# 2_-_WIDORA.net
KiCad netlist of a schematic drawn in Altium Designer
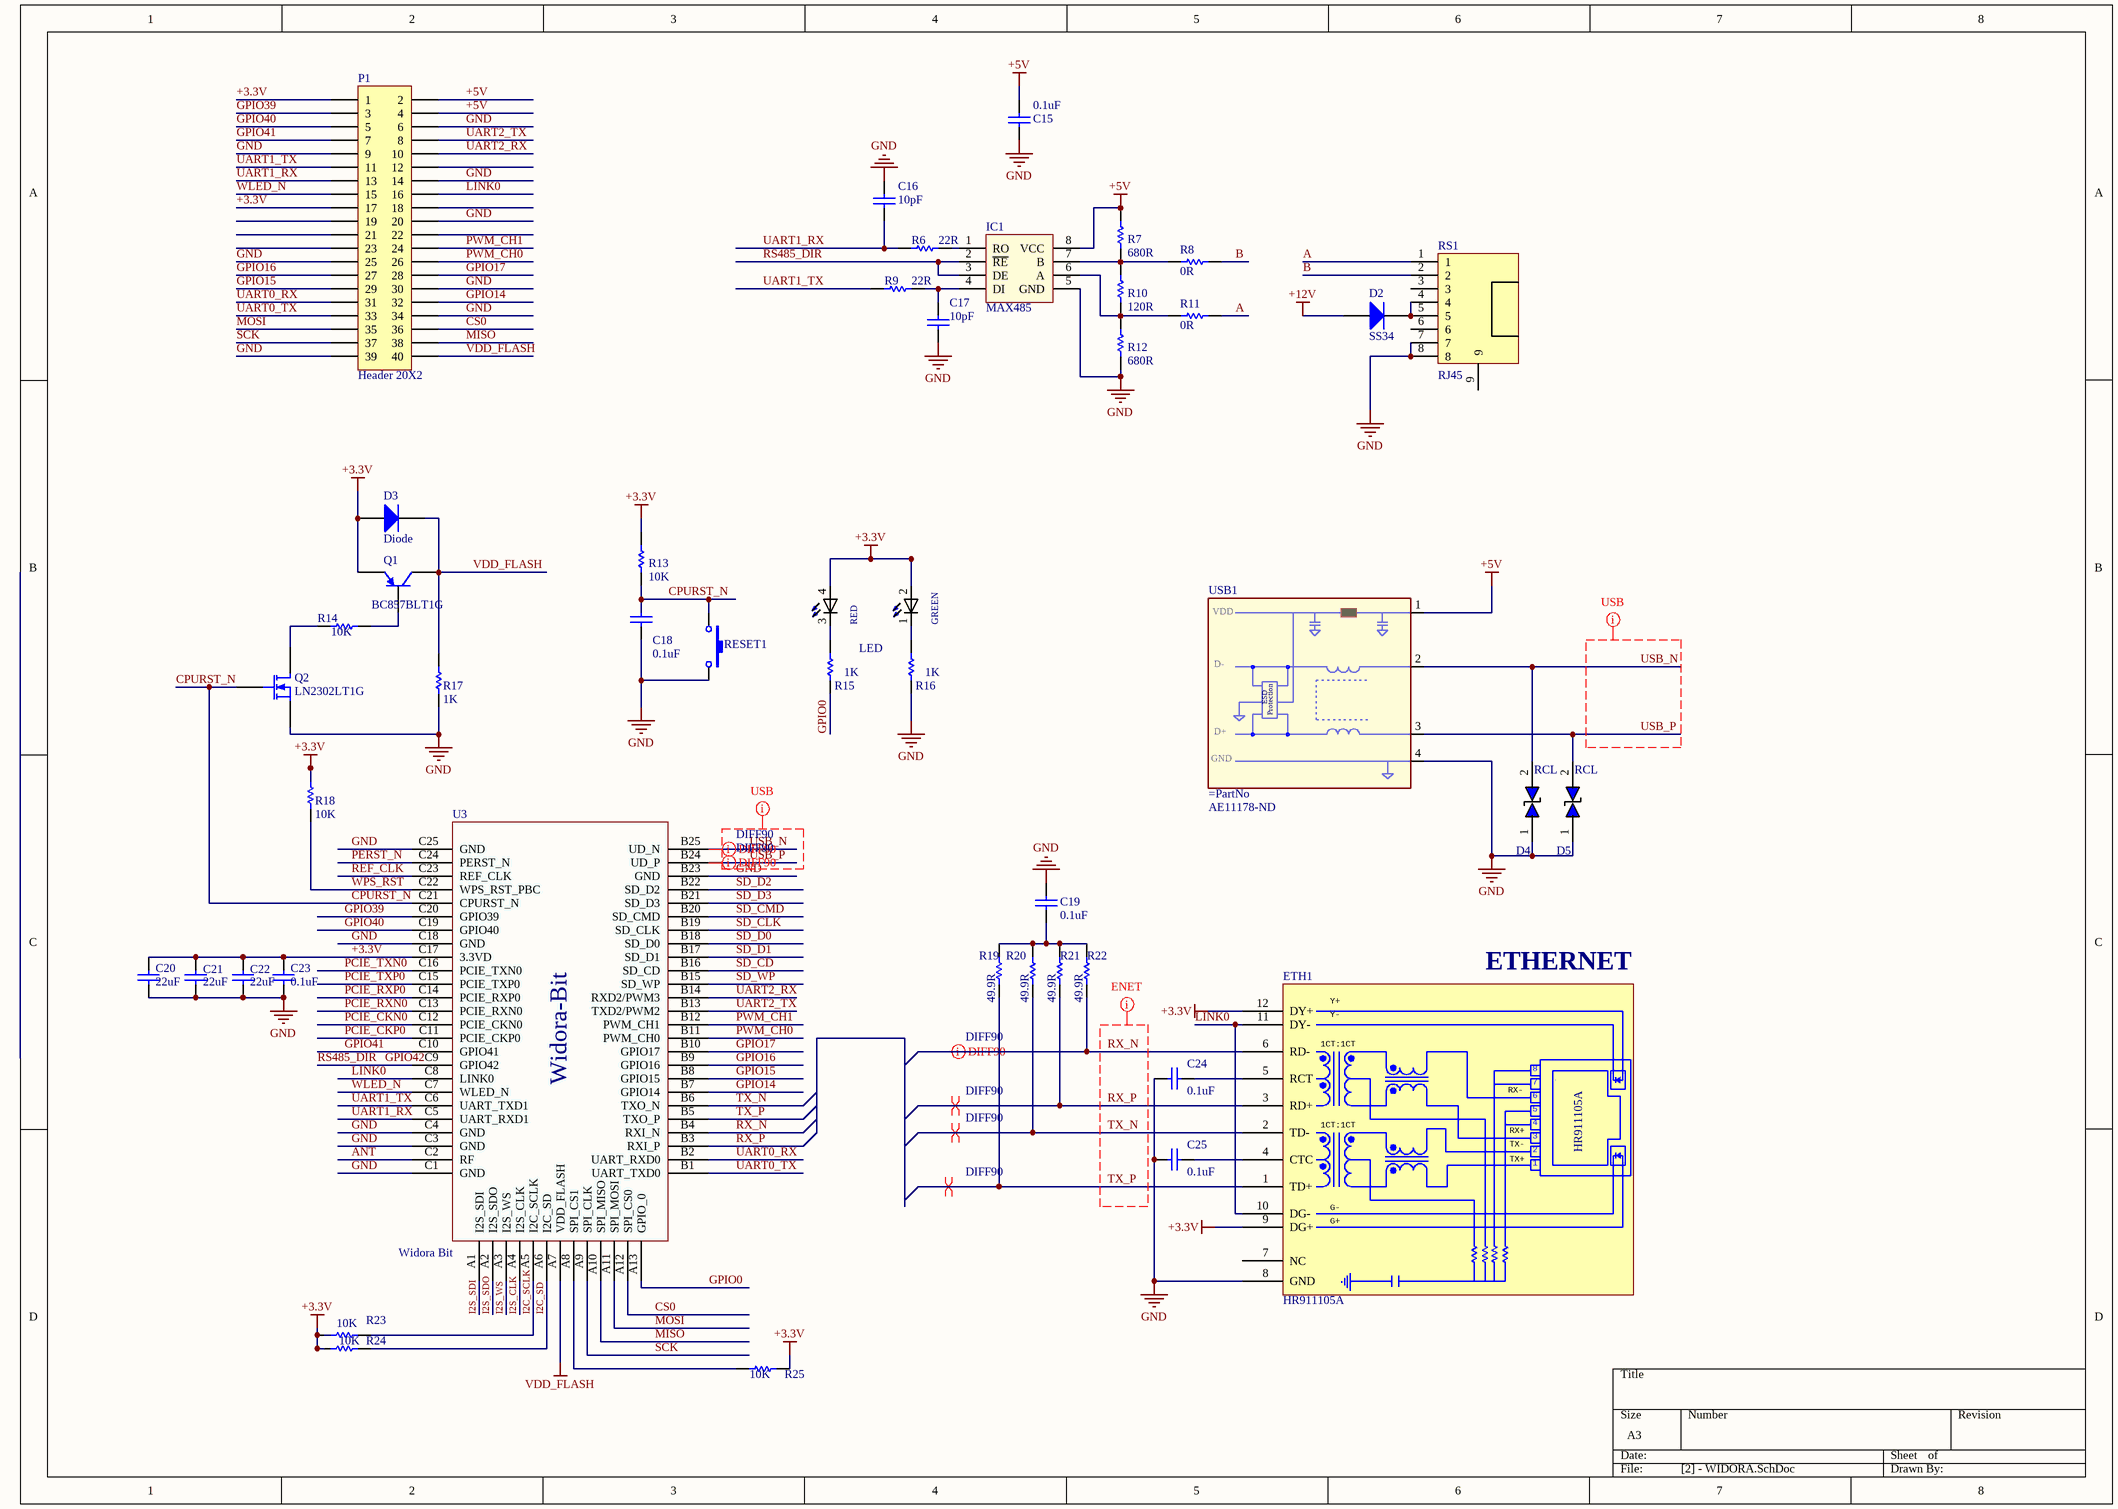
[diagram p0: [2] - WIDORA.SchDoc]

(export (version "E")
  (design (tool "Eeschema 10.0.6"))
  (components
    (comp (ref "C15")
      (value "0.1uF")
      (footprint "CN-SMD-0603")
      (description "CC0603KPX7R9BB104 0603 0.1 uF 50 V ±10% Tolerance X7R SMT Multilayer Ceramic Capacitor")
      (fields (field (name "TOLERANCE") "10%"))
      (libsource (lib "IOT_HIEP") (part "CN0603-0.1uF"))
    )
    (comp (ref "C16")
      (value "10pF")
      (footprint "CN-SMD-0603")
      (description "CC0603JRNPO9BN100 Surface Mount Ceramic Multilayer Capacitor 10pF 5% C0G 50V 0603 Paper T/R")
      (fields (field (name "TOLERANCE") "5%") (field (name "VOLTAGE") "50V"))
      (libsource (lib "IOT_HIEP") (part "CN0603-10pF"))
    )
    (comp (ref "C17")
      (value "10pF")
      (footprint "CN-SMD-0603")
      (description "CC0603JRNPO9BN100 Surface Mount Ceramic Multilayer Capacitor 10pF 5% C0G 50V 0603 Paper T/R")
      (fields (field (name "TOLERANCE") "5%") (field (name "VOLTAGE") "50V"))
      (libsource (lib "IOT_HIEP") (part "CN0603-10pF"))
    )
    (comp (ref "C18")
      (value "0.1uF")
      (footprint "CN-SMD-0603")
      (description "CC0603KPX7R9BB104 0603 0.1 uF 50 V ±10% Tolerance X7R SMT Multilayer Ceramic Capacitor")
      (fields (field (name "TOLERANCE") "10%"))
      (libsource (lib "IOT_HIEP") (part "CN0603-0.1uF"))
    )
    (comp (ref "C19")
      (value "0.1uF")
      (footprint "CN-SMD-0603")
      (description "CC0603KPX7R9BB104 0603 0.1 uF 50 V ±10% Tolerance X7R SMT Multilayer Ceramic Capacitor")
      (fields (field (name "TOLERANCE") "10%"))
      (libsource (lib "IOT_HIEP") (part "CN0603-0.1uF"))
    )
    (comp (ref "C20")
      (value "22uF")
      (footprint "CN-SMD-0805")
      (description "CC0805MKX5R6BB226 0805 22 uF 10 V ±20 % Tolerance X5R SMT Multilayer Ceramic Capacitor")
      (fields (field (name "TOLERANCE") "20%"))
      (libsource (lib "IOT_HIEP") (part "CN0805-22uF"))
    )
    (comp (ref "C21")
      (value "22uF")
      (footprint "CN-SMD-0805")
      (description "CC0805MKX5R6BB226 0805 22 uF 10 V ±20 % Tolerance X5R SMT Multilayer Ceramic Capacitor")
      (fields (field (name "TOLERANCE") "20%"))
      (libsource (lib "IOT_HIEP") (part "CN0805-22uF"))
    )
    (comp (ref "C22")
      (value "22uF")
      (footprint "CN-SMD-0805")
      (description "CC0805MKX5R6BB226 0805 22 uF 10 V ±20 % Tolerance X5R SMT Multilayer Ceramic Capacitor")
      (fields (field (name "TOLERANCE") "20%"))
      (libsource (lib "IOT_HIEP") (part "CN0805-22uF"))
    )
    (comp (ref "C23")
      (value "0.1uF")
      (footprint "CN-SMD-0603")
      (description "CC0603KPX7R9BB104 0603 0.1 uF 50 V ±10% Tolerance X7R SMT Multilayer Ceramic Capacitor")
      (fields (field (name "TOLERANCE") "10%"))
      (libsource (lib "IOT_HIEP") (part "CN0603-0.1uF"))
    )
    (comp (ref "C24")
      (value "0.1uF")
      (footprint "CN-SMD-0603")
      (description "CC0603KPX7R9BB104 0603 0.1 uF 50 V ±10% Tolerance X7R SMT Multilayer Ceramic Capacitor")
      (fields (field (name "TOLERANCE") "10%"))
      (libsource (lib "IOT_HIEP") (part "CN0603-0.1uF"))
    )
    (comp (ref "C25")
      (value "0.1uF")
      (footprint "CN-SMD-0603")
      (description "CC0603KPX7R9BB104 0603 0.1 uF 50 V ±10% Tolerance X7R SMT Multilayer Ceramic Capacitor")
      (fields (field (name "TOLERANCE") "10%"))
      (libsource (lib "IOT_HIEP") (part "CN0603-0.1uF"))
    )
    (comp (ref "D2")
      (value "SS34")
      (footprint "DO-214AC")
      (description "SS34 DIODE SCHOTTKY 40V 3A SMC")
      (fields (field (name "VOLTAGE") "40V"))
      (libsource (lib "IOT_HIEP") (part "Diode_SS34"))
    )
    (comp (ref "D3")
      (value "Diode")
      (footprint "SOD323")
      (description "Default Diode")
      (fields (field (name "PUBLISHER") "Altium Limited"))
      (libsource (lib "IOT_DAT") (part "Diode"))
    )
    (comp (ref "D4")
      (value "RCL")
      (footprint "RES-0603")
      (description "ESD Suppressor TVS Â±20KV 2-Pin SLP1006P2T T/R")
      (fields (field (name "MP") "RCLAMP0531TQTCT") (field (name "MF") "Semtech Corporation"))
      (libsource (lib "RCLAMP0531TQTCT") (part "RCLAMP0531TQTCT"))
    )
    (comp (ref "D5")
      (value "RCL")
      (footprint "RES-0603")
      (description "ESD Suppressor TVS Â±20KV 2-Pin SLP1006P2T T/R")
      (fields (field (name "MP") "RCLAMP0531TQTCT") (field (name "MF") "Semtech Corporation"))
      (libsource (lib "RCLAMP0531TQTCT") (part "RCLAMP0531TQTCT"))
    )
    (comp (ref "ETH1")
      (value "HR911105A")
      (footprint "HR911105A")
      (fields (field (name "MANUFACTURER") "Hanrun"))
      (libsource (lib "NestHouse") (part "RJ45 - Tranfomer"))
    )
    (comp (ref "IC1")
      (value "MAX485")
      (footprint "SO8")
      (description "RS232 - RS485 (Same sn75176)")
      (libsource (lib "Library AL") (part "MAX485"))
    )
    (comp (ref "LED")
      (value "122-000-04-52")
      (footprint "*122-000-04-52_122-000-04-52(Primary)")
      (fields (field (name "MF") "Marl"))
      (libsource (lib "122-000-04-52") (part "122-000-04-52"))
    )
    (comp (ref "P1")
      (value "Header 20X2")
      (footprint "HDR2X20")
      (description "Header, 20-Pin, Dual row")
      (fields (field (name "PUBLISHER") "Altium Limited"))
      (libsource (lib "IOT_DAT") (part "Header 20X2"))
    )
    (comp (ref "Q1")
      (value "BC857BLT1G")
      (footprint "SOT-23B_L")
      (description "PNP Bipolar Transistor")
      (fields
        (field (name "MANUFACTURER") "ON Semiconductor")
        (field (name "MANUFACTURER PART NUMBER") "SBC857BLT1G")
      )
      (libsource (lib "NestHouse") (part "BC857BLT1G"))
    )
    (comp (ref "Q2")
      (value "LN2302LT1G")
      (footprint "SOT-23B_L")
      (description "N-Channel MOSFET")
      (fields (field (name "MANUFACTURER") "LRC"))
      (libsource (lib "NestHouse") (part "MOSFET-N"))
    )
    (comp (ref "R6")
      (value "22R")
      (footprint "RES 0603")
      (description "311-22GRCT-ND Res Thick Film 0603 22 Ohm 5% 0.1W(1/10W) ±100ppm/C Pad SMD T/R")
      (fields (field (name "TOLERANCE") "5%"))
      (libsource (lib "IOT_HIEP") (part "RC0603_22R"))
    )
    (comp (ref "R7")
      (value "680R")
      (footprint "RES 0603")
      (description "AC0603JR-07680RL Res Thick Film 0603 680 Ohm 5% 0.1W(1/10W) +/-100ppm/ßC Epoxy SMD Automotive T/R")
      (fields (field (name "TOLERANCE") "5%"))
      (libsource (lib "IOT_HIEP") (part "RC0603_680R"))
    )
    (comp (ref "R8")
      (value "0R")
      (footprint "RES 0603")
      (description "AC0603JR-070RL Res Thick Film 0603 0 Ohm Jumper 1/10W Molded SMD Paper T/R")
      (fields (field (name "TOLERANCE") "1%"))
      (libsource (lib "IOT_HIEP") (part "RC0603_0R"))
    )
    (comp (ref "R9")
      (value "22R")
      (footprint "RES 0603")
      (description "311-22GRCT-ND Res Thick Film 0603 22 Ohm 5% 0.1W(1/10W) ±100ppm/C Pad SMD T/R")
      (fields (field (name "TOLERANCE") "5%"))
      (libsource (lib "IOT_HIEP") (part "RC0603_22R"))
    )
    (comp (ref "R10")
      (value "120R")
      (footprint "RES 0603")
      (description "RC0603JR-07120RL Res Thick Film 0603 120 Ohm 5% 0.1W(1/10W) ±100ppm/C Pad SMD T/R")
      (fields (field (name "TOLERANCE") "5%"))
      (libsource (lib "IOT_HIEP") (part "RC0603_120R"))
    )
    (comp (ref "R11")
      (value "0R")
      (footprint "RES 0603")
      (description "AC0603JR-070RL Res Thick Film 0603 0 Ohm Jumper 1/10W Molded SMD Paper T/R")
      (fields (field (name "TOLERANCE") "1%"))
      (libsource (lib "IOT_HIEP") (part "RC0603_0R"))
    )
    (comp (ref "R12")
      (value "680R")
      (footprint "RES 0603")
      (description "AC0603JR-07680RL Res Thick Film 0603 680 Ohm 5% 0.1W(1/10W) +/-100ppm/ßC Epoxy SMD Automotive T/R")
      (fields (field (name "TOLERANCE") "5%"))
      (libsource (lib "IOT_HIEP") (part "RC0603_680R"))
    )
    (comp (ref "R13")
      (value "10K")
      (footprint "RES 0603")
      (description "AC0603FR-0710KL Res Thick Film 0603 10K Ohm 1% 0.1W(1/10W) ±100ppm/C Pad SMD Automotive T/R")
      (fields (field (name "TOLERANCE") "1%"))
      (libsource (lib "IOT_HIEP") (part "RC0603_10K"))
    )
    (comp (ref "R14")
      (value "10K")
      (footprint "RES 0603")
      (description "AC0603FR-0710KL Res Thick Film 0603 10K Ohm 1% 0.1W(1/10W) ±100ppm/C Pad SMD Automotive T/R")
      (fields (field (name "TOLERANCE") "1%") (field (name "SUPPLIER PART NUMBER 1") "10K"))
      (libsource (lib "IOT_HIEP") (part "RC0603_10K"))
    )
    (comp (ref "R15")
      (value "1K")
      (footprint "RES 0603")
      (fields (field (name "TOLERANCE") "5%"))
      (libsource (lib "IOT_HIEP") (part "RC0603_1K"))
    )
    (comp (ref "R16")
      (value "1K")
      (footprint "RES 0603")
      (fields (field (name "TOLERANCE") "5%"))
      (libsource (lib "IOT_HIEP") (part "RC0603_1K"))
    )
    (comp (ref "R17")
      (value "1K")
      (footprint "RES 0603")
      (fields (field (name "TOLERANCE") "5%"))
      (libsource (lib "IOT_HIEP") (part "RC0603_1K"))
    )
    (comp (ref "R18")
      (value "10K")
      (footprint "RES 0603")
      (description "AC0603FR-0710KL Res Thick Film 0603 10K Ohm 1% 0.1W(1/10W) ±100ppm/C Pad SMD Automotive T/R")
      (fields (field (name "TOLERANCE") "1%"))
      (libsource (lib "IOT_HIEP") (part "RC0603_10K"))
    )
    (comp (ref "R19")
      (value "49.9R")
      (footprint "RES 0603")
      (description "YAG5744CT-ND Res Thin Film 0603 49.9 Ohm 1% 1/10W ±50ppm/°C Molded SMD SMD Paper T/R")
      (fields (field (name "TOLERANCE") "1%"))
      (libsource (lib "IOT_HIEP") (part "RC0603_49.9R"))
    )
    (comp (ref "R20")
      (value "49.9R")
      (footprint "RES 0603")
      (description "YAG5744CT-ND Res Thin Film 0603 49.9 Ohm 1% 1/10W ±50ppm/°C Molded SMD SMD Paper T/R")
      (fields (field (name "TOLERANCE") "1%"))
      (libsource (lib "IOT_HIEP") (part "RC0603_49.9R"))
    )
    (comp (ref "R21")
      (value "49.9R")
      (footprint "RES 0603")
      (description "YAG5744CT-ND Res Thin Film 0603 49.9 Ohm 1% 1/10W ±50ppm/°C Molded SMD SMD Paper T/R")
      (fields (field (name "TOLERANCE") "1%"))
      (libsource (lib "IOT_HIEP") (part "RC0603_49.9R"))
    )
    (comp (ref "R22")
      (value "49.9R")
      (footprint "RES 0603")
      (description "YAG5744CT-ND Res Thin Film 0603 49.9 Ohm 1% 1/10W ±50ppm/°C Molded SMD SMD Paper T/R")
      (fields (field (name "TOLERANCE") "1%"))
      (libsource (lib "IOT_HIEP") (part "RC0603_49.9R"))
    )
    (comp (ref "R23")
      (value "10K")
      (footprint "RES 0603")
      (description "AC0603FR-0710KL Res Thick Film 0603 10K Ohm 1% 0.1W(1/10W) ±100ppm/C Pad SMD Automotive T/R")
      (fields (field (name "TOLERANCE") "1%"))
      (libsource (lib "IOT_HIEP") (part "RC0603_10K"))
    )
    (comp (ref "R24")
      (value "10K")
      (footprint "RES 0603")
      (description "AC0603FR-0710KL Res Thick Film 0603 10K Ohm 1% 0.1W(1/10W) ±100ppm/C Pad SMD Automotive T/R")
      (fields (field (name "TOLERANCE") "1%"))
      (libsource (lib "IOT_HIEP") (part "RC0603_10K"))
    )
    (comp (ref "R25")
      (value "10K")
      (footprint "RES 0603")
      (description "AC0603FR-0710KL Res Thick Film 0603 10K Ohm 1% 0.1W(1/10W) ±100ppm/C Pad SMD Automotive T/R")
      (fields (field (name "TOLERANCE") "1%"))
      (libsource (lib "IOT_HIEP") (part "RC0603_10K"))
    )
    (comp (ref "RESET1")
      (value "SW-SMD")
      (footprint "SW2-D2 - duplicate")
      (description "Switch")
      (fields (field (name "PUBLISHER") "Altium Limited"))
      (libsource (lib "NBBLib 14-03-2012") (part "SW-SMD"))
    )
    (comp (ref "RS1")
      (value "RJ45")
      (footprint "RJ45_8PIN_VOSAT_V2")
      (libsource (lib "Library_HoangAnh") (part "RJ45"))
    )
    (comp (ref "U3")
      (value "Widora Bit")
      (footprint "WIDORA")
      (description "Widora MT7688")
      (fields
        (field (name "MANUFACTURER") "Widora")
        (field (name "MANUFACTURER PART NUMBER") "Widora Bit 3 MT7688")
      )
      (libsource (lib "NestHouse") (part "Widora"))
    )
    (comp (ref "USB1")
      (value "~")
      (footprint "USB A Vertical")
      (description "THT USB 2.0 A Connector WE-EPLE")
      (fields
        (field (name "MANUFACTURER") "ASSMANN WSW Components")
        (field (name "MANUFACTURER PART NUMBER") "A-USB A-E")
        (field (name "SUPPLIER PART NUMBER 1") "AE11178-ND")
      )
      (libsource (lib "NestHouse") (part "USB-4"))
    )
  )
  (nets
    (net (code "1") (name "+3.3V") (class "Default")
      (node (ref "C20") (pin "2") (pinfunction "2_2") (pintype "passive"))
      (node (ref "C21") (pin "2") (pinfunction "2_2") (pintype "passive"))
      (node (ref "C22") (pin "2") (pinfunction "2_2") (pintype "passive"))
      (node (ref "C23") (pin "1") (pinfunction "1_1") (pintype "passive"))
      (node (ref "D3") (pin "1") (pinfunction "A_1") (pintype "passive"))
      (node (ref "ETH1") (pin "12") (pinfunction "DY+_12") (pintype "passive"))
      (node (ref "ETH1") (pin "9") (pinfunction "DG+_9") (pintype "passive"))
      (node (ref "LED") (pin "2") (pinfunction "GA_2") (pintype "passive"))
      (node (ref "LED") (pin "4") (pinfunction "RA_4") (pintype "passive"))
      (node (ref "P1") (pin "1") (pinfunction "1_1") (pintype "passive"))
      (node (ref "P1") (pin "17") (pinfunction "17_17") (pintype "passive"))
      (node (ref "Q1") (pin "2") (pinfunction "E_2") (pintype "passive"))
      (node (ref "R13") (pin "2") (pinfunction "2_2") (pintype "passive"))
      (node (ref "R18") (pin "2") (pinfunction "2_2") (pintype "passive"))
      (node (ref "R23") (pin "2") (pinfunction "2_2") (pintype "passive"))
      (node (ref "R24") (pin "2") (pinfunction "2_2") (pintype "passive"))
      (node (ref "R25") (pin "1") (pinfunction "1_1") (pintype "passive"))
      (node (ref "U3") (pin "C17") (pinfunction "3.3VD_C17") (pintype "passive"))
    )
    (net (code "2") (name "+5V") (class "Default")
      (node (ref "C15") (pin "2") (pinfunction "2_2") (pintype "passive"))
      (node (ref "IC1") (pin "8") (pinfunction "VCC_8") (pintype "passive"))
      (node (ref "P1") (pin "2") (pinfunction "2_2") (pintype "passive"))
      (node (ref "P1") (pin "4") (pinfunction "4_4") (pintype "passive"))
      (node (ref "R7") (pin "2") (pinfunction "2_2") (pintype "passive"))
      (node (ref "USB1") (pin "1") (pinfunction "VBUS_1") (pintype "passive"))
    )
    (net (code "3") (name "+12V") (class "Default")
      (node (ref "D2") (pin "1") (pinfunction "A_1") (pintype "passive"))
    )
    (net (code "4") (name "/A") (class "Default")
      (node (ref "R11") (pin "2") (pinfunction "2_2") (pintype "passive"))
      (node (ref "RS1") (pin "1") (pinfunction "1_1") (pintype "passive"))
    )
    (net (code "5") (name "/ANT") (class "Default")
      (node (ref "U3") (pin "C2") (pinfunction "RF_C2") (pintype "passive"))
    )
    (net (code "6") (name "/B") (class "Default")
      (node (ref "R8") (pin "2") (pinfunction "2_2") (pintype "passive"))
      (node (ref "RS1") (pin "2") (pinfunction "2_2") (pintype "passive"))
    )
    (net (code "7") (name "/CPURST_N") (class "Default")
      (node (ref "C18") (pin "2") (pinfunction "2_2") (pintype "passive"))
      (node (ref "Q2") (pin "1") (pinfunction "G_1") (pintype "passive"))
      (node (ref "R13") (pin "1") (pinfunction "1_1") (pintype "passive"))
      (node (ref "RESET1") (pin "1") (pinfunction "1_1") (pintype "passive"))
      (node (ref "U3") (pin "C21") (pinfunction "CPURST_N_C21") (pintype "passive"))
    )
    (net (code "8") (name "/CS0") (class "Default")
      (node (ref "P1") (pin "36") (pinfunction "36_36") (pintype "passive"))
      (node (ref "U3") (pin "A12") (pinfunction "SPI_CS0_A12") (pintype "passive"))
    )
    (net (code "9") (name "/GPIO0") (class "Default")
      (node (ref "R15") (pin "1") (pinfunction "1_1") (pintype "passive"))
      (node (ref "U3") (pin "A13") (pinfunction "GPIO_0_A13") (pintype "passive"))
    )
    (net (code "10") (name "/GPIO14") (class "Default")
      (node (ref "P1") (pin "32") (pinfunction "32_32") (pintype "passive"))
      (node (ref "U3") (pin "B7") (pinfunction "GPIO14_B7") (pintype "passive"))
    )
    (net (code "11") (name "/GPIO15") (class "Default")
      (node (ref "P1") (pin "29") (pinfunction "29_29") (pintype "passive"))
      (node (ref "U3") (pin "B8") (pinfunction "GPIO15_B8") (pintype "passive"))
    )
    (net (code "12") (name "/GPIO16") (class "Default")
      (node (ref "P1") (pin "27") (pinfunction "27_27") (pintype "passive"))
      (node (ref "U3") (pin "B9") (pinfunction "GPIO16_B9") (pintype "passive"))
    )
    (net (code "13") (name "/GPIO17") (class "Default")
      (node (ref "P1") (pin "28") (pinfunction "28_28") (pintype "passive"))
      (node (ref "U3") (pin "B10") (pinfunction "GPIO17_B10") (pintype "passive"))
    )
    (net (code "14") (name "/GPIO39") (class "Default")
      (node (ref "P1") (pin "3") (pinfunction "3_3") (pintype "passive"))
      (node (ref "U3") (pin "C20") (pinfunction "GPIO39_C20") (pintype "passive"))
    )
    (net (code "15") (name "/GPIO40") (class "Default")
      (node (ref "P1") (pin "5") (pinfunction "5_5") (pintype "passive"))
      (node (ref "U3") (pin "C19") (pinfunction "GPIO40_C19") (pintype "passive"))
    )
    (net (code "16") (name "/GPIO41") (class "Default")
      (node (ref "P1") (pin "7") (pinfunction "7_7") (pintype "passive"))
      (node (ref "U3") (pin "C10") (pinfunction "GPIO41_C10") (pintype "passive"))
    )
    (net (code "17") (name "/GPIO42") (class "Default")
      (node (ref "IC1") (pin "2") (pinfunction "~{RE}_2") (pintype "passive"))
      (node (ref "IC1") (pin "3") (pinfunction "DE_3") (pintype "passive"))
      (node (ref "U3") (pin "C9") (pinfunction "GPIO42_C9") (pintype "passive"))
    )
    (net (code "18") (name "/I2C_SCLK") (class "Default")
      (node (ref "R23") (pin "1") (pinfunction "1_1") (pintype "passive"))
      (node (ref "U3") (pin "A5") (pinfunction "I2C_SCLK_A5") (pintype "passive"))
    )
    (net (code "19") (name "/I2C_SD") (class "Default")
      (node (ref "R24") (pin "1") (pinfunction "1_1") (pintype "passive"))
      (node (ref "U3") (pin "A6") (pinfunction "I2C_SD_A6") (pintype "passive"))
    )
    (net (code "20") (name "/I2S_CLK") (class "Default")
      (node (ref "U3") (pin "A4") (pinfunction "I2S_CLK_A4") (pintype "passive"))
    )
    (net (code "21") (name "/I2S_SDI") (class "Default")
      (node (ref "U3") (pin "A1") (pinfunction "I2S_SDI_A1") (pintype "passive"))
    )
    (net (code "22") (name "/I2S_SDO") (class "Default")
      (node (ref "U3") (pin "A2") (pinfunction "I2S_SDO_A2") (pintype "passive"))
    )
    (net (code "23") (name "/I2S_WS") (class "Default")
      (node (ref "U3") (pin "A3") (pinfunction "I2S_WS_A3") (pintype "passive"))
    )
    (net (code "24") (name "/LINK0") (class "Default")
      (node (ref "ETH1") (pin "10") (pinfunction "DG-_10") (pintype "passive"))
      (node (ref "ETH1") (pin "11") (pinfunction "DY-_11") (pintype "passive"))
      (node (ref "P1") (pin "16") (pinfunction "16_16") (pintype "passive"))
      (node (ref "U3") (pin "C8") (pinfunction "LINK0_C8") (pintype "passive"))
    )
    (net (code "25") (name "/MISO") (class "Default")
      (node (ref "P1") (pin "38") (pinfunction "38_38") (pintype "passive"))
      (node (ref "U3") (pin "A10") (pinfunction "SPI_MISO_A10") (pintype "passive"))
    )
    (net (code "26") (name "/MOSI") (class "Default")
      (node (ref "P1") (pin "35") (pinfunction "35_35") (pintype "passive"))
      (node (ref "U3") (pin "A11") (pinfunction "SPI_MOSI_A11") (pintype "passive"))
    )
    (net (code "27") (name "/PCIE_CKN0") (class "Default")
      (node (ref "U3") (pin "C12") (pinfunction "PCIE_CKN0_C12") (pintype "passive"))
    )
    (net (code "28") (name "/PCIE_CKP0") (class "Default")
      (node (ref "U3") (pin "C11") (pinfunction "PCIE_CKP0_C11") (pintype "passive"))
    )
    (net (code "29") (name "/PCIE_RXN0") (class "Default")
      (node (ref "U3") (pin "C13") (pinfunction "PCIE_RXN0_C13") (pintype "passive"))
    )
    (net (code "30") (name "/PCIE_RXP0") (class "Default")
      (node (ref "U3") (pin "C14") (pinfunction "PCIE_RXP0_C14") (pintype "passive"))
    )
    (net (code "31") (name "/PCIE_TXN0") (class "Default")
      (node (ref "U3") (pin "C16") (pinfunction "PCIE_TXN0_C16") (pintype "passive"))
    )
    (net (code "32") (name "/PCIE_TXP0") (class "Default")
      (node (ref "U3") (pin "C15") (pinfunction "PCIE_TXP0_C15") (pintype "passive"))
    )
    (net (code "33") (name "/PERST_N") (class "Default")
      (node (ref "U3") (pin "C24") (pinfunction "PERST_N_C24") (pintype "passive"))
    )
    (net (code "34") (name "/PWM_CH0") (class "Default")
      (node (ref "P1") (pin "26") (pinfunction "26_26") (pintype "passive"))
      (node (ref "U3") (pin "B11") (pinfunction "PWM_CH0_B11") (pintype "passive"))
    )
    (net (code "35") (name "/PWM_CH1") (class "Default")
      (node (ref "P1") (pin "24") (pinfunction "24_24") (pintype "passive"))
      (node (ref "U3") (pin "B12") (pinfunction "PWM_CH1_B12") (pintype "passive"))
    )
    (net (code "36") (name "/REF_CLK") (class "Default")
      (node (ref "U3") (pin "C23") (pinfunction "REF_CLK_C23") (pintype "passive"))
    )
    (net (code "37") (name "/RX_N") (class "Default")
      (node (ref "ETH1") (pin "6") (pinfunction "RD-_6") (pintype "passive"))
      (node (ref "R22") (pin "2") (pinfunction "2_2") (pintype "passive"))
      (node (ref "U3") (pin "B4") (pinfunction "RXI_N_B4") (pintype "passive"))
    )
    (net (code "38") (name "/RX_P") (class "Default")
      (node (ref "ETH1") (pin "3") (pinfunction "RD+_3") (pintype "passive"))
      (node (ref "R21") (pin "2") (pinfunction "2_2") (pintype "passive"))
      (node (ref "U3") (pin "B3") (pinfunction "RXI_P_B3") (pintype "passive"))
    )
    (net (code "39") (name "/SCK") (class "Default")
      (node (ref "P1") (pin "37") (pinfunction "37_37") (pintype "passive"))
      (node (ref "U3") (pin "A9") (pinfunction "SPI_CLK_A9") (pintype "passive"))
    )
    (net (code "40") (name "/SD_CD") (class "Default")
      (node (ref "U3") (pin "B16") (pinfunction "SD_CD_B16") (pintype "passive"))
    )
    (net (code "41") (name "/SD_CLK") (class "Default")
      (node (ref "U3") (pin "B19") (pinfunction "SD_CLK_B19") (pintype "passive"))
    )
    (net (code "42") (name "/SD_CMD") (class "Default")
      (node (ref "U3") (pin "B20") (pinfunction "SD_CMD_B20") (pintype "passive"))
    )
    (net (code "43") (name "/SD_D0") (class "Default")
      (node (ref "U3") (pin "B18") (pinfunction "SD_D0_B18") (pintype "passive"))
    )
    (net (code "44") (name "/SD_D1") (class "Default")
      (node (ref "U3") (pin "B17") (pinfunction "SD_D1_B17") (pintype "passive"))
    )
    (net (code "45") (name "/SD_D2") (class "Default")
      (node (ref "U3") (pin "B22") (pinfunction "SD_D2_B22") (pintype "passive"))
    )
    (net (code "46") (name "/SD_D3") (class "Default")
      (node (ref "U3") (pin "B21") (pinfunction "SD_D3_B21") (pintype "passive"))
    )
    (net (code "47") (name "/SD_WP") (class "Default")
      (node (ref "U3") (pin "B15") (pinfunction "SD_WP_B15") (pintype "passive"))
    )
    (net (code "48") (name "/TX_N") (class "Default")
      (node (ref "ETH1") (pin "2") (pinfunction "TD-_2") (pintype "passive"))
      (node (ref "R20") (pin "2") (pinfunction "2_2") (pintype "passive"))
      (node (ref "U3") (pin "B6") (pinfunction "TXO_N_B6") (pintype "passive"))
    )
    (net (code "49") (name "/TX_P") (class "Default")
      (node (ref "ETH1") (pin "1") (pinfunction "TD+_1") (pintype "passive"))
      (node (ref "R19") (pin "2") (pinfunction "2_2") (pintype "passive"))
      (node (ref "U3") (pin "B5") (pinfunction "TXO_P_B5") (pintype "passive"))
    )
    (net (code "50") (name "/UART0_RX") (class "Default")
      (node (ref "P1") (pin "31") (pinfunction "31_31") (pintype "passive"))
      (node (ref "U3") (pin "B2") (pinfunction "UART_RXD0_B2") (pintype "passive"))
    )
    (net (code "51") (name "/UART0_TX") (class "Default")
      (node (ref "P1") (pin "33") (pinfunction "33_33") (pintype "passive"))
      (node (ref "U3") (pin "B1") (pinfunction "UART_TXD0_B1") (pintype "passive"))
    )
    (net (code "52") (name "/UART1_RX") (class "Default")
      (node (ref "C16") (pin "1") (pinfunction "1_1") (pintype "passive"))
      (node (ref "P1") (pin "13") (pinfunction "13_13") (pintype "passive"))
      (node (ref "R6") (pin "2") (pinfunction "2_2") (pintype "passive"))
      (node (ref "U3") (pin "C5") (pinfunction "UART_RXD1_C5") (pintype "passive"))
    )
    (net (code "53") (name "/UART1_TX") (class "Default")
      (node (ref "P1") (pin "11") (pinfunction "11_11") (pintype "passive"))
      (node (ref "R9") (pin "2") (pinfunction "2_2") (pintype "passive"))
      (node (ref "U3") (pin "C6") (pinfunction "UART_TXD1_C6") (pintype "passive"))
    )
    (net (code "54") (name "/UART2_RX") (class "Default")
      (node (ref "P1") (pin "10") (pinfunction "10_10") (pintype "passive"))
      (node (ref "U3") (pin "B14") (pinfunction "RXD2/PWM3_B14") (pintype "passive"))
    )
    (net (code "55") (name "/UART2_TX") (class "Default")
      (node (ref "P1") (pin "8") (pinfunction "8_8") (pintype "passive"))
      (node (ref "U3") (pin "B13") (pinfunction "TXD2/PWM2_B13") (pintype "passive"))
    )
    (net (code "56") (name "/USB_N") (class "Default")
      (node (ref "D4") (pin "2") (pinfunction "2_2") (pintype "passive"))
      (node (ref "U3") (pin "B25") (pinfunction "UD_N_B25") (pintype "passive"))
      (node (ref "USB1") (pin "2") (pinfunction "D-_2") (pintype "passive"))
    )
    (net (code "57") (name "/USB_P") (class "Default")
      (node (ref "D5") (pin "2") (pinfunction "2_2") (pintype "passive"))
      (node (ref "U3") (pin "B24") (pinfunction "UD_P_B24") (pintype "passive"))
      (node (ref "USB1") (pin "3") (pinfunction "D+_3") (pintype "passive"))
    )
    (net (code "58") (name "/WLED_N") (class "Default")
      (node (ref "P1") (pin "15") (pinfunction "15_15") (pintype "passive"))
      (node (ref "U3") (pin "C7") (pinfunction "WLED_N_C7") (pintype "passive"))
    )
    (net (code "59") (name "/WPS_RST") (class "Default")
      (node (ref "R18") (pin "1") (pinfunction "1_1") (pintype "passive"))
      (node (ref "U3") (pin "C22") (pinfunction "WPS_RST_PBC_C22") (pintype "passive"))
    )
    (net (code "60") (name "GND") (class "Default")
      (node (ref "C15") (pin "1") (pinfunction "1_1") (pintype "passive"))
      (node (ref "C16") (pin "2") (pinfunction "2_2") (pintype "passive"))
      (node (ref "C17") (pin "2") (pinfunction "2_2") (pintype "passive"))
      (node (ref "C18") (pin "1") (pinfunction "1_1") (pintype "passive"))
      (node (ref "C19") (pin "2") (pinfunction "2_2") (pintype "passive"))
      (node (ref "C20") (pin "1") (pinfunction "1_1") (pintype "passive"))
      (node (ref "C21") (pin "1") (pinfunction "1_1") (pintype "passive"))
      (node (ref "C22") (pin "1") (pinfunction "1_1") (pintype "passive"))
      (node (ref "C23") (pin "2") (pinfunction "2_2") (pintype "passive"))
      (node (ref "C24") (pin "2") (pinfunction "2_2") (pintype "passive"))
      (node (ref "C25") (pin "2") (pinfunction "2_2") (pintype "passive"))
      (node (ref "D4") (pin "1") (pinfunction "1_1") (pintype "passive"))
      (node (ref "D5") (pin "1") (pinfunction "1_1") (pintype "passive"))
      (node (ref "ETH1") (pin "8") (pinfunction "GND_8") (pintype "power_in"))
      (node (ref "IC1") (pin "5") (pinfunction "GND_5") (pintype "passive"))
      (node (ref "P1") (pin "14") (pinfunction "14_14") (pintype "passive"))
      (node (ref "P1") (pin "20") (pinfunction "20_20") (pintype "passive"))
      (node (ref "P1") (pin "25") (pinfunction "25_25") (pintype "passive"))
      (node (ref "P1") (pin "30") (pinfunction "30_30") (pintype "passive"))
      (node (ref "P1") (pin "34") (pinfunction "34_34") (pintype "passive"))
      (node (ref "P1") (pin "39") (pinfunction "39_39") (pintype "passive"))
      (node (ref "P1") (pin "6") (pinfunction "6_6") (pintype "passive"))
      (node (ref "P1") (pin "9") (pinfunction "9_9") (pintype "passive"))
      (node (ref "Q2") (pin "2") (pinfunction "S_2") (pintype "passive"))
      (node (ref "R12") (pin "1") (pinfunction "1_1") (pintype "passive"))
      (node (ref "R16") (pin "1") (pinfunction "1_1") (pintype "passive"))
      (node (ref "R17") (pin "1") (pinfunction "1_1") (pintype "passive"))
      (node (ref "RESET1") (pin "2") (pinfunction "2_2") (pintype "passive"))
      (node (ref "RS1") (pin "7") (pinfunction "7_7") (pintype "passive"))
      (node (ref "RS1") (pin "8") (pinfunction "8_8") (pintype "passive"))
      (node (ref "U3") (pin "B23") (pinfunction "GND_B23") (pintype "passive"))
      (node (ref "U3") (pin "C1") (pinfunction "GND_C1") (pintype "passive"))
      (node (ref "U3") (pin "C18") (pinfunction "GND_C18") (pintype "passive"))
      (node (ref "U3") (pin "C25") (pinfunction "GND_C25") (pintype "passive"))
      (node (ref "U3") (pin "C3") (pinfunction "GND_C3") (pintype "passive"))
      (node (ref "U3") (pin "C4") (pinfunction "GND_C4") (pintype "passive"))
      (node (ref "USB1") (pin "4") (pinfunction "GND_4") (pintype "passive"))
    )
    (net (code "61") (name "Net-(C19-Pad1)") (class "Default")
      (node (ref "C19") (pin "1") (pinfunction "1_1") (pintype "passive"))
      (node (ref "R19") (pin "1") (pinfunction "1_1") (pintype "passive"))
      (node (ref "R20") (pin "1") (pinfunction "1_1") (pintype "passive"))
      (node (ref "R21") (pin "1") (pinfunction "1_1") (pintype "passive"))
      (node (ref "R22") (pin "1") (pinfunction "1_1") (pintype "passive"))
    )
    (net (code "62") (name "Net-(D2-K)") (class "Default")
      (node (ref "D2") (pin "2") (pinfunction "K_2") (pintype "passive"))
      (node (ref "RS1") (pin "4") (pinfunction "4_4") (pintype "passive"))
      (node (ref "RS1") (pin "5") (pinfunction "5_5") (pintype "passive"))
    )
    (net (code "63") (name "Net-(ETH1-CTC)") (class "Default")
      (node (ref "C25") (pin "1") (pinfunction "1_1") (pintype "passive"))
      (node (ref "ETH1") (pin "4") (pinfunction "CTC_4") (pintype "passive"))
    )
    (net (code "64") (name "Net-(ETH1-RCT)") (class "Default")
      (node (ref "C24") (pin "1") (pinfunction "1_1") (pintype "passive"))
      (node (ref "ETH1") (pin "5") (pinfunction "RCT_5") (pintype "passive"))
    )
    (net (code "65") (name "Net-(IC1-A)") (class "Default")
      (node (ref "IC1") (pin "6") (pinfunction "A_6") (pintype "passive"))
      (node (ref "R10") (pin "1") (pinfunction "1_1") (pintype "passive"))
      (node (ref "R11") (pin "1") (pinfunction "1_1") (pintype "passive"))
      (node (ref "R12") (pin "2") (pinfunction "2_2") (pintype "passive"))
    )
    (net (code "66") (name "Net-(IC1-B)") (class "Default")
      (node (ref "IC1") (pin "7") (pinfunction "B_7") (pintype "passive"))
      (node (ref "R10") (pin "2") (pinfunction "2_2") (pintype "passive"))
      (node (ref "R7") (pin "1") (pinfunction "1_1") (pintype "passive"))
      (node (ref "R8") (pin "1") (pinfunction "1_1") (pintype "passive"))
    )
    (net (code "67") (name "Net-(IC1-DI)") (class "Default")
      (node (ref "C17") (pin "1") (pinfunction "1_1") (pintype "passive"))
      (node (ref "IC1") (pin "4") (pinfunction "DI_4") (pintype "passive"))
      (node (ref "R9") (pin "1") (pinfunction "1_1") (pintype "passive"))
    )
    (net (code "68") (name "Net-(IC1-RO)") (class "Default")
      (node (ref "IC1") (pin "1") (pinfunction "RO_1") (pintype "passive"))
      (node (ref "R6") (pin "1") (pinfunction "1_1") (pintype "passive"))
    )
    (net (code "69") (name "Net-(LED-GC)") (class "Default")
      (node (ref "LED") (pin "1") (pinfunction "GC_1") (pintype "passive"))
      (node (ref "R16") (pin "2") (pinfunction "2_2") (pintype "passive"))
    )
    (net (code "70") (name "Net-(LED-RC)") (class "Default")
      (node (ref "LED") (pin "3") (pinfunction "RC_3") (pintype "passive"))
      (node (ref "R15") (pin "2") (pinfunction "2_2") (pintype "passive"))
    )
    (net (code "71") (name "Net-(Q1-B)") (class "Default")
      (node (ref "Q1") (pin "1") (pinfunction "B_1") (pintype "passive"))
      (node (ref "R14") (pin "2") (pinfunction "2_2") (pintype "passive"))
    )
    (net (code "72") (name "Net-(Q2-D)") (class "Default")
      (node (ref "Q2") (pin "3") (pinfunction "D_3") (pintype "passive"))
      (node (ref "R14") (pin "1") (pinfunction "1_1") (pintype "passive"))
    )
    (net (code "73") (name "Net-(U3-SPI_CS1)") (class "Default")
      (node (ref "R25") (pin "2") (pinfunction "2_2") (pintype "passive"))
      (node (ref "U3") (pin "A8") (pinfunction "SPI_CS1_A8") (pintype "passive"))
    )
    (net (code "74") (name "VDD_FLASH") (class "Default")
      (node (ref "D3") (pin "2") (pinfunction "K_2") (pintype "passive"))
      (node (ref "P1") (pin "40") (pinfunction "40_40") (pintype "passive"))
      (node (ref "Q1") (pin "3") (pinfunction "C_3") (pintype "passive"))
      (node (ref "R17") (pin "2") (pinfunction "2_2") (pintype "passive"))
      (node (ref "U3") (pin "A7") (pinfunction "VDD_FLASH_A7") (pintype "passive"))
    )
    (net (code "75") (name "unconnected-(ETH1-NC-Pad7)") (class "Default")
      (node (ref "ETH1") (pin "7") (pinfunction "NC_7") (pintype "passive"))
    )
    (net (code "76") (name "unconnected-(P1-Pad12)") (class "Default")
      (node (ref "P1") (pin "12") (pinfunction "12_12") (pintype "passive"))
    )
    (net (code "77") (name "unconnected-(P1-Pad18)") (class "Default")
      (node (ref "P1") (pin "18") (pinfunction "18_18") (pintype "passive"))
    )
    (net (code "78") (name "unconnected-(P1-Pad19)") (class "Default")
      (node (ref "P1") (pin "19") (pinfunction "19_19") (pintype "passive"))
    )
    (net (code "79") (name "unconnected-(P1-Pad21)") (class "Default")
      (node (ref "P1") (pin "21") (pinfunction "21_21") (pintype "passive"))
    )
    (net (code "80") (name "unconnected-(P1-Pad22)") (class "Default")
      (node (ref "P1") (pin "22") (pinfunction "22_22") (pintype "passive"))
    )
    (net (code "81") (name "unconnected-(P1-Pad23)") (class "Default")
      (node (ref "P1") (pin "23") (pinfunction "23_23") (pintype "passive"))
    )
    (net (code "82") (name "unconnected-(RS1-Pad3)") (class "Default")
      (node (ref "RS1") (pin "3") (pinfunction "3_3") (pintype "passive"))
    )
    (net (code "83") (name "unconnected-(RS1-Pad6)") (class "Default")
      (node (ref "RS1") (pin "6") (pinfunction "6_6") (pintype "passive"))
    )
    (net (code "84") (name "unconnected-(RS1-Pad9)") (class "Default")
      (node (ref "RS1") (pin "9") (pinfunction "9_9") (pintype "passive"))
    )
  )
)
